# 01-USB_Device.net
KiCad netlist of a schematic drawn in Altium Designer
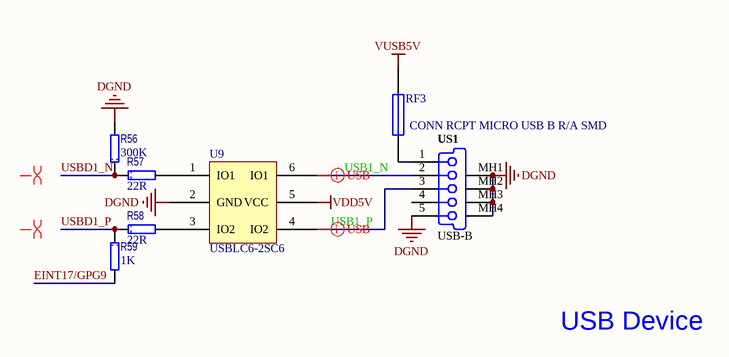
[diagram p0: 01-USB Device.SchDoc]

(export (version "E")
  (design (tool "Eeschema 10.0.6"))
  (components
    (comp (ref "R56")
      (value "300K")
      (footprint "1608[0603]R")
      (description "厚膜电阻器 - SMD 1/10watt 300Kohms 1%")
      (fields
        (field (name "MANUFACTURER") "Vishay / Dale")
        (field (name "MANUFACTURER PART NUMBER") "CRCW0603300KFKEA")
      )
      (libsource (lib "300K 1%") (part "RES"))
    )
    (comp (ref "R57")
      (value "22R")
      (footprint "1608[0603]R")
      (description "厚膜电阻器 - SMD 1/10watt 22ohms 1%")
      (fields
        (field (name "MANUFACTURER") "Vishay / Dale")
        (field (name "MANUFACTURER PART NUMBER") "CRCW060322R0FKEA")
      )
      (libsource (lib "22R 1%") (part "RES"))
    )
    (comp (ref "R58")
      (value "22R")
      (footprint "1608[0603]R")
      (description "厚膜电阻器 - SMD 1/10watt 22ohms 1%")
      (fields
        (field (name "MANUFACTURER") "Vishay / Dale")
        (field (name "MANUFACTURER PART NUMBER") "CRCW060322R0FKEA")
      )
      (libsource (lib "22R 1%") (part "RES"))
    )
    (comp (ref "R59")
      (value "1K")
      (footprint "1608[0603]R")
      (description "厚膜电阻器 - SMD 1/10watt 1.0Kohms 1%")
      (fields
        (field (name "MANUFACTURER") "Vishay / Dale")
        (field (name "MANUFACTURER PART NUMBER") "CRCW06031K00FKEA")
      )
      (libsource (lib "1K 1%") (part "RES"))
    )
    (comp (ref "RF3")
      (value "0805L050WR")
      (footprint "2012[0805]F")
      (description "可复位保险丝 PTC 30V POLY SURF MOUNT 0805 .500A")
      (fields (field (name "MANUFACTURER") "Littelfuse"))
      (libsource (lib "*") (part "FUSE1"))
    )
    (comp (ref "U9")
      (value "USBLC6-2SC6")
      (footprint "SOT26A-6N")
      (description "TVS二极管阵列 ESD Protection Low Cap")
      (fields (field (name "MANUFACTURER") "STMicroelectronics"))
      (libsource (lib "S3C2440V9") (part "USBLC6-2SC6"))
    )
    (comp (ref "US1")
      (value "USB-B")
      (footprint "USB/SM0.8-6H5")
      (fields
        (field (name "MANUFACTURER") "TE Connectivity")
        (field (name "MANUFACTURER PART NUMBER") "1981568-1")
        (field (name "DESCRIPTION 1") "CONN RCPT MICRO USB B R/A SMD")
      )
      (libsource (lib "AltiumDesignLibrary") (part "0481900001"))
    )
  )
  (nets
    (net (code "1") (name "/EINT17{slash}GPG9") (class "Default")
      (node (ref "R59") (pin "2") (pinfunction "2_2") (pintype "passive"))
    )
    (net (code "2") (name "/USB1_N") (class "Default")
      (node (ref "U9") (pin "6") (pinfunction "IO1_6") (pintype "passive"))
      (node (ref "US1") (pin "2") (pinfunction "2_2") (pintype "passive"))
    )
    (net (code "3") (name "/USB1_P") (class "Default")
      (node (ref "U9") (pin "4") (pinfunction "IO2_4") (pintype "passive"))
      (node (ref "US1") (pin "3") (pinfunction "3_3") (pintype "passive"))
    )
    (net (code "4") (name "/USBD1_N") (class "Default")
      (node (ref "R56") (pin "1") (pinfunction "1_1") (pintype "passive"))
      (node (ref "R57") (pin "1") (pinfunction "1_1") (pintype "passive"))
    )
    (net (code "5") (name "/USBD1_P") (class "Default")
      (node (ref "R58") (pin "1") (pinfunction "1_1") (pintype "passive"))
      (node (ref "R59") (pin "1") (pinfunction "1_1") (pintype "passive"))
    )
    (net (code "6") (name "DGND") (class "Default")
      (node (ref "R56") (pin "2") (pinfunction "2_2") (pintype "passive"))
      (node (ref "U9") (pin "2") (pinfunction "GND_2") (pintype "passive"))
      (node (ref "US1") (pin "5") (pinfunction "5_5") (pintype "passive"))
      (node (ref "US1") (pin "MH1") (pinfunction "MH1_MH1") (pintype "passive"))
      (node (ref "US1") (pin "MH2") (pinfunction "MH2_MH2") (pintype "passive"))
      (node (ref "US1") (pin "MH3") (pinfunction "MH3_MH3") (pintype "passive"))
      (node (ref "US1") (pin "MH4") (pinfunction "MH4_MH4") (pintype "passive"))
    )
    (net (code "7") (name "Net-(R57-Pad2)") (class "Default")
      (node (ref "R57") (pin "2") (pinfunction "2_2") (pintype "passive"))
      (node (ref "U9") (pin "1") (pinfunction "IO1_1") (pintype "passive"))
    )
    (net (code "8") (name "Net-(R58-Pad2)") (class "Default")
      (node (ref "R58") (pin "2") (pinfunction "2_2") (pintype "passive"))
      (node (ref "U9") (pin "3") (pinfunction "IO2_3") (pintype "passive"))
    )
    (net (code "9") (name "Net-(RF3-Pad1)") (class "Default")
      (node (ref "RF3") (pin "1") (pinfunction "1_1") (pintype "passive"))
      (node (ref "US1") (pin "1") (pinfunction "1_1") (pintype "passive"))
    )
    (net (code "10") (name "VDD5V") (class "Default")
      (node (ref "U9") (pin "5") (pinfunction "VCC_5") (pintype "passive"))
    )
    (net (code "11") (name "VUSB5V") (class "Default")
      (node (ref "RF3") (pin "2") (pinfunction "2_2") (pintype "passive"))
    )
    (net (code "12") (name "unconnected-(US1-Pad4)") (class "Default")
      (node (ref "US1") (pin "4") (pinfunction "4_4") (pintype "passive"))
    )
  )
)
